# DB_LEDS.net
KiCad netlist of a schematic drawn in Altium Designer
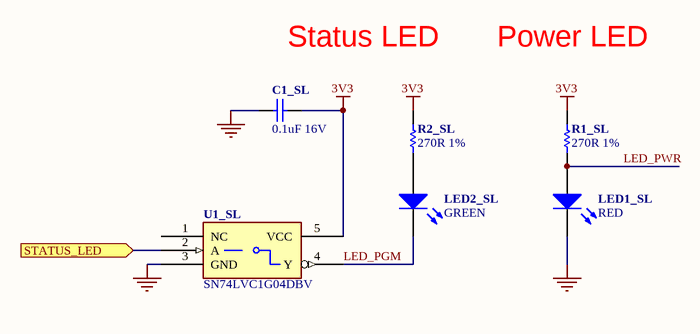
[diagram p0: DB_LEDS.SchDoc]

(export (version "E")
  (design (tool "Eeschema 10.0.6"))
  (components
    (comp (ref "C1_SL")
      (value "0.1uF 16V")
      (footprint "CAPC1005-STAR")
      (description "Capacitor, Ceramic, 0.1uF 10% 16V 0402 (1005) X7R")
      (fields (field (name "TOLERANCE") "10 %"))
      (libsource (lib "AltiumDesignLibrary") (part "CAP-NP"))
    )
    (comp (ref "LED1_SL")
      (value "RED")
      (footprint "LED2012-STAR")
      (description "LED, Red 0805 (2013) HSMH-C170")
      (libsource (lib "AltiumDesignLibrary") (part "DIO-LED-1S"))
    )
    (comp (ref "LED2_SL")
      (value "GREEN")
      (footprint "LED2012-STAR")
      (description "LED, Green 0805 (2012) KP-2012SGD")
      (libsource (lib "AltiumDesignLibrary") (part "DIO-LED-1S"))
    )
    (comp (ref "R1_SL")
      (value "270R 1%")
      (footprint "RESC1005-STAR")
      (description "Resistor, 270R 1% 0402 (1005)")
      (fields (field (name "TOLERANCE") "1 %"))
      (libsource (lib "AltiumDesignLibrary") (part "RES"))
    )
    (comp (ref "R2_SL")
      (value "270R 1%")
      (footprint "RESC1005-STAR")
      (description "Resistor, 270R 1% 0402 (1005)")
      (fields (field (name "TOLERANCE") "1 %"))
      (libsource (lib "AltiumDesignLibrary") (part "RES"))
    )
    (comp (ref "U1_SL")
      (value "SN74LVC1G04DBV")
      (footprint "SOT95P280-5")
      (description "SN74LVC1G04DBV, Single Inverter Gate, 1.65-V to 5.5-V")
      (libsource (lib "AltiumDesignLibrary") (part "SN74LVC1G04DBV"))
    )
  )
  (nets
    (net (code "1") (name "/LED_PGM") (class "Default")
      (node (ref "LED2_SL") (pin "2") (pinfunction "K_2") (pintype "passive"))
      (node (ref "U1_SL") (pin "4") (pinfunction "Y_4") (pintype "output"))
    )
    (net (code "2") (name "/LED_PWR") (class "Default")
      (node (ref "LED1_SL") (pin "1") (pinfunction "A_1") (pintype "passive"))
      (node (ref "R1_SL") (pin "2") (pinfunction "2_2") (pintype "passive"))
    )
    (net (code "3") (name "/STATUS_LED") (class "Default")
      (node (ref "U1_SL") (pin "2") (pinfunction "A_2") (pintype "input"))
    )
    (net (code "4") (name "3V3") (class "Default")
      (node (ref "C1_SL") (pin "2") (pinfunction "2_2") (pintype "passive"))
      (node (ref "R1_SL") (pin "1") (pinfunction "1_1") (pintype "passive"))
      (node (ref "R2_SL") (pin "1") (pinfunction "1_1") (pintype "passive"))
      (node (ref "U1_SL") (pin "5") (pinfunction "VCC_5") (pintype "power_in"))
    )
    (net (code "5") (name "GND") (class "Default")
      (node (ref "C1_SL") (pin "1") (pinfunction "1_1") (pintype "passive"))
      (node (ref "LED1_SL") (pin "2") (pinfunction "K_2") (pintype "passive"))
      (node (ref "U1_SL") (pin "3") (pinfunction "GND_3") (pintype "power_in"))
    )
    (net (code "6") (name "Net-(LED2_SL-A)") (class "Default")
      (node (ref "LED2_SL") (pin "1") (pinfunction "A_1") (pintype "passive"))
      (node (ref "R2_SL") (pin "2") (pinfunction "2_2") (pintype "passive"))
    )
    (net (code "7") (name "unconnected-(U1_SL-NC-Pad1)") (class "Default")
      (node (ref "U1_SL") (pin "1") (pinfunction "NC_1") (pintype "passive"))
    )
  )
)
